# POWER.net
KiCad netlist of a schematic drawn in Altium Designer
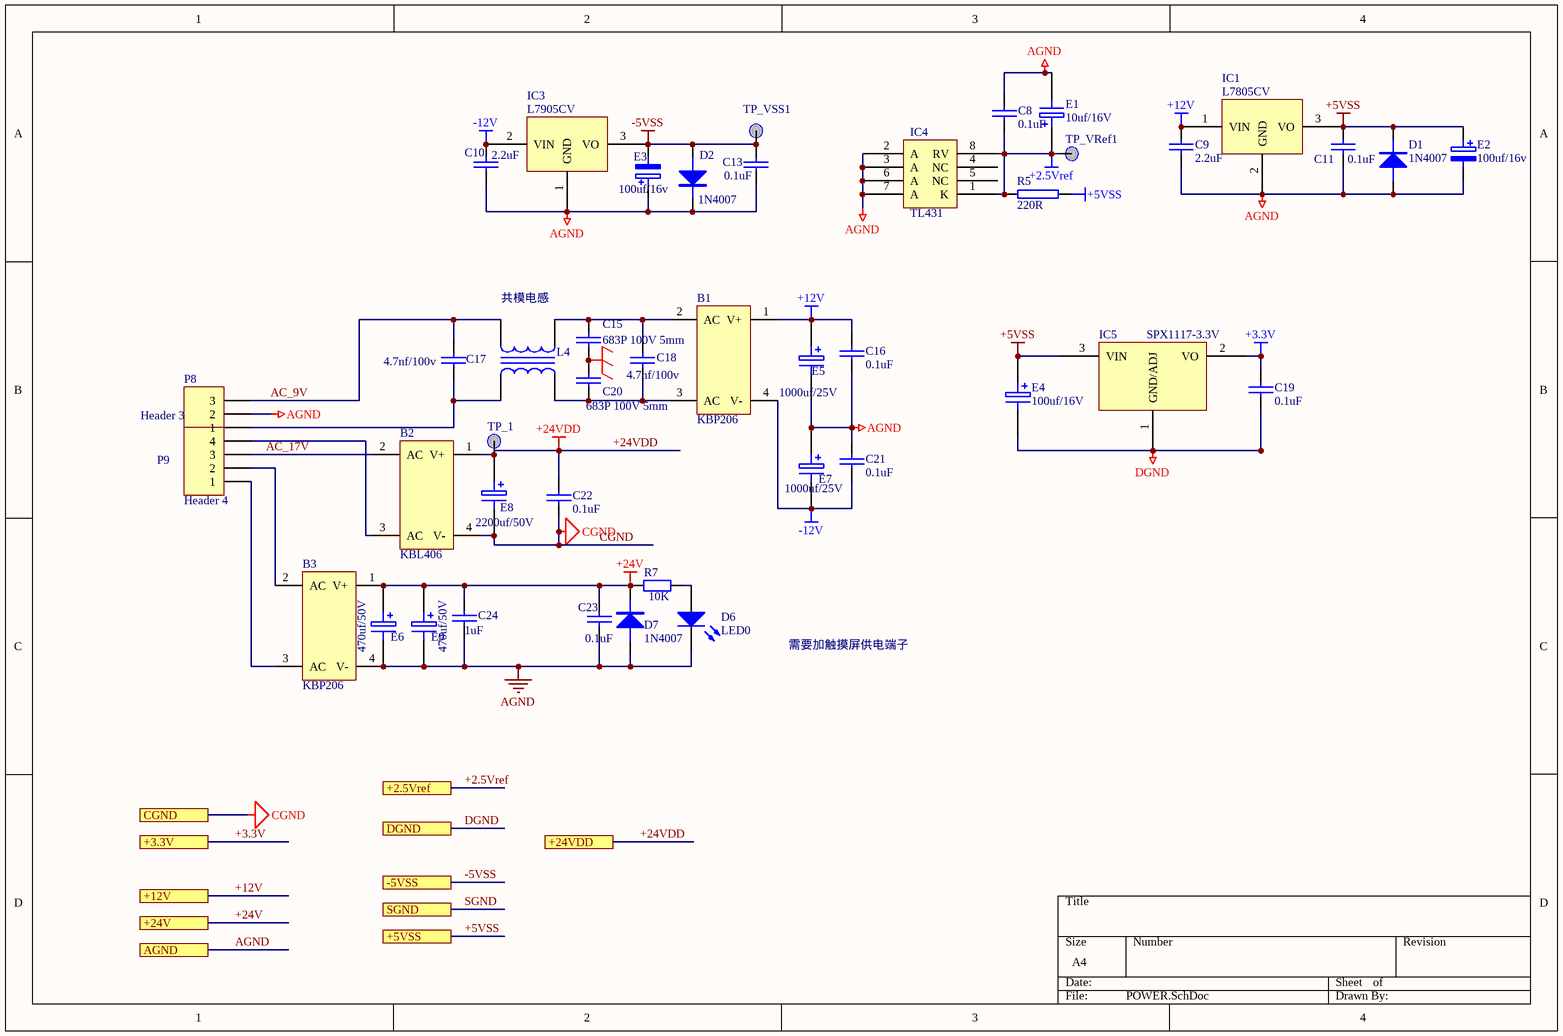
[diagram p0: POWER.SchDoc]

(export (version "E")
  (design (tool "Eeschema 10.0.6"))
  (components
    (comp (ref "B1")
      (value "KBP206")
      (footprint "KBP206")
      (description "品牌： MDD  型号： KBP206  直流反向耐压(Vr)：600V 平均整流电流(Io)：2A 正向压降(Vf)：1.1V@2A 正向浪涌电流(Ifsm)：60A")
      (libsource (lib "*") (part "BRIDGE"))
    )
    (comp (ref "B2")
      (value "KBL406")
      (footprint "KPL406")
      (description "品牌： MDD  型号： KBL406  直流反向耐压(Vr)：600V 平均整流电流(Io)：4A 正向压降(Vf)：1V@4A 正向浪涌电流(Ifsm)：125A")
      (libsource (lib "*") (part "BRIDGE"))
    )
    (comp (ref "B3")
      (value "KBP206")
      (footprint "KBP206")
      (description "品牌： MDD  型号： KBP206  直流反向耐压(Vr)：600V 平均整流电流(Io)：2A 正向压降(Vf)：1.1V@2A 正向浪涌电流(Ifsm)：60A")
      (libsource (lib "*") (part "BRIDGE"))
    )
    (comp (ref "C8") (value "0.1uF") (footprint "0805C") (libsource (lib "*") (part "CAP")))
    (comp (ref "C9")
      (value "2.2uF")
      (footprint "0805C")
      (description "品牌： SAMSUNG(三星) 型号： CL21B225KAFNNNE 容值：2.2uF 精度：±10% 额定电压：25V 材质(温度系数)：X7R 材质:X7R")
      (libsource (lib "*") (part "CAP"))
    )
    (comp (ref "C10")
      (value "2.2uF")
      (footprint "0805C")
      (description "品牌： SAMSUNG(三星) 型号： CL21B225KAFNNNE 容值：2.2uF 精度：±10% 额定电压：25V 材质(温度系数)：X7R 材质:X7R")
      (libsource (lib "*") (part "CAP"))
    )
    (comp (ref "C11")
      (value "0.1uF")
      (footprint "0805C")
      (description "品牌： SAMSUNG(三星) 型号： CL21B104KBCNNNC ：容值：100nF 精度：±10% 额定电压：50V 材质(温度系数)：X7R 材质:X7R")
      (libsource (lib "*") (part "CAP"))
    )
    (comp (ref "C13")
      (value "0.1uF")
      (footprint "0805C")
      (description "品牌： SAMSUNG(三星)    型号： CL10B104KB8NNNC  容值：100nF 精度：±10% 额定电压：50V 材质(温度系数)：X7R 材质:X7R")
      (libsource (lib "*") (part "CAP"))
    )
    (comp (ref "C15")
      (value "683P 100V 5mm")
      (footprint "CP1")
      (description "品牌： muRata(村田) 型号： RCER72A683K1K1H03B  容值：68nF 精度：±10% 额定电压：100V 温度系数：X7R")
      (libsource (lib "*") (part "CAP"))
    )
    (comp (ref "C16")
      (value "0.1uF")
      (footprint "0805C")
      (description "品牌： SAMSUNG(三星)    型号： CL10B104KB8NNNC  容值：100nF 精度：±10% 额定电压：50V 材质(温度系数)：X7R 材质:X7R")
      (libsource (lib "*") (part "CAP"))
    )
    (comp (ref "C17")
      (value "4.7nf/100v")
      (footprint "CP1")
      (description "品牌： muRata(村田) 品牌： muRata(村田)  容值：4.7nF 精度：±10% 额定电压：100V 温度系数：X7R")
      (libsource (lib "*") (part "CAP"))
    )
    (comp (ref "C18")
      (value "4.7nf/100v")
      (footprint "CP1")
      (description "品牌： muRata(村田) 品牌： muRata(村田)  容值：4.7nF 精度：±10% 额定电压：100V 温度系数：X7R")
      (libsource (lib "*") (part "CAP"))
    )
    (comp (ref "C19")
      (value "0.1uF")
      (footprint "0805C")
      (description "Capacitor")
      (libsource (lib "*") (part "CAP"))
    )
    (comp (ref "C20")
      (value "683P 100V 5mm")
      (footprint "CP1")
      (description "品牌： muRata(村田) 型号： RCER72A683K1K1H03B  容值：68nF 精度：±10% 额定电压：100V 温度系数：X7R")
      (libsource (lib "*") (part "CAP"))
    )
    (comp (ref "C21")
      (value "0.1uF")
      (footprint "0805C")
      (description "品牌： SAMSUNG(三星)    型号： CL10B104KB8NNNC  容值：100nF 精度：±10% 额定电压：50V 材质(温度系数)：X7R 材质:X7R")
      (libsource (lib "*") (part "CAP"))
    )
    (comp (ref "C22")
      (value "0.1uF")
      (footprint "0805C")
      (description "品牌： SAMSUNG(三星) 型号： CL21B104KBCNNNC ：容值：100nF 精度：±10% 额定电压：50V 材质(温度系数)：X7R 材质:X7R")
      (libsource (lib "*") (part "CAP"))
    )
    (comp (ref "C23")
      (value "0.1uF")
      (footprint "0805C")
      (description "品牌： SAMSUNG(三星) 型号： CL21B104KBCNNNC ：容值：100nF 精度：±10% 额定电压：50V 材质(温度系数)：X7R 材质:X7R")
      (libsource (lib "*") (part "CAP"))
    )
    (comp (ref "C24")
      (value "1uF")
      (footprint "0805C")
      (description "品牌： SAMSUNG(三星) 型号： CL21B334KBFNNNE 容值：330nF 精度：±10% 额定电压：50V 材质(温度系数)：X7R 材质:X7R")
      (libsource (lib "*") (part "CAP"))
    )
    (comp (ref "D1") (value "1N4007") (footprint "SK24") (libsource (lib "*") (part "DIODE")))
    (comp (ref "D2") (value "1N4007") (footprint "SK24") (libsource (lib "*") (part "DIODE")))
    (comp (ref "D6")
      (value "LED0")
      (footprint "0805LED")
      (description "品牌： 国星光电 型号： NCD0805B2 发光颜色：蓝灯 贴片LED；0805蓝色；2012蓝色；透镜颜色：无色透明；发光角度：130°；功率：72mW；工作温度：-30℃~+85℃；")
      (fields (field (name "PUBLISHER") "Altium Limited"))
      (libsource (lib "Miscellaneous Devices") (part "LED0"))
    )
    (comp (ref "D7") (value "1N4007") (footprint "SK24") (libsource (lib "*") (part "DIODE")))
    (comp (ref "E1")
      (value "10uf/16V")
      (footprint "3528")
      (description "品牌： Kyocera AVX 型号： TAJB106K016RNJ ：容值：10uF 精度：±10% 额定电压：16V 等效串联电阻：2.8Ω@100kHz")
      (libsource (lib "*") (part "ELECTRO1"))
    )
    (comp (ref "E2")
      (value "100uf/16v")
      (footprint "3528")
      (description "品牌： Kyocera AVX 型号： TAJB107M010RNJ  容值：100uF 精度：±20% 额定电压：10V 等效串联电阻：1.4Ω@100kHz")
      (libsource (lib "*") (part "ELECTRO2"))
    )
    (comp (ref "E3")
      (value "100uf/16v")
      (footprint "3528")
      (description "品牌： Kyocera AVX 型号： TAJB107M010RNJ  容值：100uF 精度：±20% 额定电压：10V 等效串联电阻：1.4Ω@100kHz")
      (libsource (lib "*") (part "ELECTRO2"))
    )
    (comp (ref "E4")
      (value "100uf/16V")
      (footprint "3528")
      (description "Electrolytic Capacitor")
      (libsource (lib "*") (part "ELECTRO1"))
    )
    (comp (ref "E5")
      (value "1000uf/25V")
      (footprint "EC5.08-10.5")
      (description "品牌： CX(承兴) 型号： KM108M025G17RR0VH2FP0 容值：1000uF 精度：±20% 额定电压：25V")
      (libsource (lib "*") (part "ELECTRO1"))
    )
    (comp (ref "E6")
      (value "470uf/50V")
      (footprint "EC5.08-10.5")
      (description "品牌： CX(承兴) 型号： KM108M025G17RR0VH2FP0 容值：1000uF 精度：±20% 额定电压：25V")
      (libsource (lib "*") (part "ELECTRO1"))
    )
    (comp (ref "E7")
      (value "1000uf/25V")
      (footprint "EC5.08-10.5")
      (description "品牌： CX(承兴) 型号： KM108M025G17RR0VH2FP0 容值：1000uF 精度：±20% 额定电压：25V")
      (libsource (lib "*") (part "ELECTRO1"))
    )
    (comp (ref "E8")
      (value "2200uf/50V")
      (footprint "EC5.08-13.5")
      (description "品牌： CX(承兴) 型号： KM228M050K30RR0VH2FP0 容值：2200uF 精度：±20% 额定电压：50V")
      (libsource (lib "*") (part "ELECTRO1"))
    )
    (comp (ref "E9")
      (value "470uf/50V")
      (footprint "EC5.08-10.5")
      (description "品牌： CX(承兴) 型号： KM108M025G17RR0VH2FP0 容值：1000uF 精度：±20% 额定电压：25V")
      (libsource (lib "*") (part "ELECTRO1"))
    )
    (comp (ref "IC1")
      (value "L7805CV")
      (footprint "DPAK3")
      (description "品牌： UMW(友台半导体)  型号： L7805CV  输出类型：固定 输出极性：正 最大输入电压：35V 输出电压：5V 输出电流：1.2A")
      (libsource (lib "*") (part "MC78XX"))
    )
    (comp (ref "IC3") (value "L7905CV") (footprint "DPAK3") (libsource (lib "*") (part "MC79XX")))
    (comp (ref "IC4")
      (value "TL431")
      (footprint "SO8")
      (description "品牌： JSMSEMI(杰盛微) 型号： TL431输出类型：可调 输入电压：37V 输出电压：2.5V~36V")
      (libsource (lib "*") (part "TL431-SO8"))
    )
    (comp (ref "IC5") (value "SPX1117-3.3V") (footprint "SOT223") (libsource (lib "*") (part "SPX1117")))
    (comp (ref "L4")
      (value "共模电感")
      (footprint "TRANS")
      (description "UF16 22mH 1.5A 12.5*10")
      (libsource (lib "*") (part "TRANS1"))
    )
    (comp (ref "P8")
      (value "Header 3")
      (footprint "CONN-TH-KF7.62-3P")
      (fields (field (name "PUBLISHER") "Altium Limited"))
      (libsource (lib "Miscellaneous Connectors") (part "Header 3"))
    )
    (comp (ref "P9")
      (value "Header 4")
      (footprint "CONN-TH_KF7.62-4P")
      (fields (field (name "PUBLISHER") "Altium Limited"))
      (libsource (lib "Miscellaneous Connectors") (part "Header 4"))
    )
    (comp (ref "R5")
      (value "220R")
      (footprint "0805R")
      (description "品牌： UNI-ROYAL(厚声) 型号： 0805W8J0221T5E 电阻类型：厚膜电阻 阻值：220Ω 精度：±5% 功率：125mW 温度系数：±100ppm/℃")
      (libsource (lib "*") (part "RES2"))
    )
    (comp (ref "R7")
      (value "10K")
      (footprint "0805R")
      (description "品牌： UNI-ROYAL(厚声) 型号： 0805W8F1002T5E 电阻类型：厚膜电阻 阻值：10kΩ 精度：±1% 功率：125mW 温度系数：±100ppm/℃")
      (fields (field (name "PUBLISHER") "Altium Limited"))
      (libsource (lib "Miscellaneous Devices") (part "Res2"))
    )
    (comp (ref "TP_1") (value "~") (footprint "TPP") (libsource (lib "*") (part "TP")))
    (comp (ref "TP_VRef1") (value "~") (footprint "TPP") (libsource (lib "*") (part "TP")))
    (comp (ref "TP_VSS1") (value "~") (footprint "TPP") (libsource (lib "*") (part "TP")))
  )
  (nets
    (net (code "1") (name "+2.5Vref") (class "Default")
      (node (ref "C8") (pin "2") (pinfunction "2_2") (pintype "passive"))
      (node (ref "E1") (pin "1") (pinfunction "1_1") (pintype "passive"))
      (node (ref "IC4") (pin "1") (pinfunction "K_1") (pintype "passive"))
      (node (ref "IC4") (pin "8") (pinfunction "RV_8") (pintype "passive"))
      (node (ref "R5") (pin "1") (pinfunction "1_1") (pintype "passive"))
      (node (ref "TP_VRef1") (pin "1") (pinfunction "1_1") (pintype "passive"))
    )
    (net (code "2") (name "+3.3V") (class "Default")
      (node (ref "C19") (pin "1") (pinfunction "1_1") (pintype "passive"))
      (node (ref "IC5") (pin "2") (pinfunction "VO_2") (pintype "passive"))
    )
    (net (code "3") (name "+5VSS") (class "Default")
      (node (ref "C11") (pin "1") (pinfunction "1_1") (pintype "passive"))
      (node (ref "D1") (pin "2") (pinfunction "K_2") (pintype "passive"))
      (node (ref "E2") (pin "1") (pintype "passive"))
      (node (ref "E4") (pin "1") (pinfunction "1_1") (pintype "passive"))
      (node (ref "IC1") (pin "3") (pinfunction "VO_3") (pintype "passive"))
      (node (ref "IC5") (pin "3") (pinfunction "VIN_3") (pintype "passive"))
      (node (ref "R5") (pin "2") (pinfunction "2_2") (pintype "passive"))
    )
    (net (code "4") (name "+12V") (class "Default")
      (node (ref "B1") (pin "1") (pinfunction "V+_1") (pintype "passive"))
      (node (ref "C16") (pin "1") (pinfunction "1_1") (pintype "passive"))
      (node (ref "C9") (pin "1") (pinfunction "1_1") (pintype "passive"))
      (node (ref "E5") (pin "1") (pinfunction "1_1") (pintype "passive"))
      (node (ref "IC1") (pin "1") (pinfunction "VIN_1") (pintype "passive"))
    )
    (net (code "5") (name "+24V") (class "Default")
      (node (ref "B3") (pin "1") (pinfunction "V+_1") (pintype "passive"))
      (node (ref "C23") (pin "1") (pinfunction "1_1") (pintype "passive"))
      (node (ref "C24") (pin "1") (pinfunction "1_1") (pintype "passive"))
      (node (ref "D7") (pin "2") (pinfunction "K_2") (pintype "passive"))
      (node (ref "E6") (pin "1") (pinfunction "1_1") (pintype "passive"))
      (node (ref "E9") (pin "1") (pinfunction "1_1") (pintype "passive"))
      (node (ref "R7") (pin "2") (pinfunction "2_2") (pintype "passive"))
    )
    (net (code "6") (name "+24VDD") (class "Default")
      (node (ref "B2") (pin "1") (pinfunction "V+_1") (pintype "passive"))
      (node (ref "C22") (pin "1") (pinfunction "1_1") (pintype "passive"))
      (node (ref "E8") (pin "1") (pinfunction "1_1") (pintype "passive"))
      (node (ref "TP_1") (pin "1") (pinfunction "1_1") (pintype "passive"))
    )
    (net (code "7") (name "-5VSS") (class "Default")
      (node (ref "C13") (pin "1") (pinfunction "1_1") (pintype "passive"))
      (node (ref "D2") (pin "1") (pinfunction "A_1") (pintype "passive"))
      (node (ref "E3") (pin "2") (pintype "passive"))
      (node (ref "IC3") (pin "3") (pinfunction "VO_3") (pintype "passive"))
      (node (ref "TP_VSS1") (pin "1") (pinfunction "1_1") (pintype "passive"))
    )
    (net (code "8") (name "-12V") (class "Default")
      (node (ref "B1") (pin "4") (pinfunction "V-_4") (pintype "passive"))
      (node (ref "C10") (pin "1") (pinfunction "1_1") (pintype "passive"))
      (node (ref "C21") (pin "2") (pinfunction "2_2") (pintype "passive"))
      (node (ref "E7") (pin "2") (pinfunction "2_2") (pintype "passive"))
      (node (ref "IC3") (pin "2") (pinfunction "VIN_2") (pintype "passive"))
    )
    (net (code "10") (name "/AC_9V") (class "Default")
      (node (ref "C17") (pin "1") (pinfunction "1_1") (pintype "passive"))
      (node (ref "L4") (pin "2") (pinfunction "2_2") (pintype "passive"))
      (node (ref "P8") (pin "3") (pinfunction "3_3") (pintype "passive"))
    )
    (net (code "11") (name "/AC_17V") (class "Default")
      (node (ref "B2") (pin "2") (pinfunction "AC_2") (pintype "passive"))
      (node (ref "P9") (pin "3") (pinfunction "3_3") (pintype "passive"))
    )
    (net (code "13") (name "AGND") (class "Default")
      (node (ref "B3") (pin "4") (pinfunction "V-_4") (pintype "passive"))
      (node (ref "C10") (pin "2") (pinfunction "2_2") (pintype "passive"))
      (node (ref "C11") (pin "2") (pinfunction "2_2") (pintype "passive"))
      (node (ref "C13") (pin "2") (pinfunction "2_2") (pintype "passive"))
      (node (ref "C16") (pin "2") (pinfunction "2_2") (pintype "passive"))
      (node (ref "C21") (pin "1") (pinfunction "1_1") (pintype "passive"))
      (node (ref "C23") (pin "2") (pinfunction "2_2") (pintype "passive"))
      (node (ref "C24") (pin "2") (pinfunction "2_2") (pintype "passive"))
      (node (ref "C8") (pin "1") (pinfunction "1_1") (pintype "passive"))
      (node (ref "C9") (pin "2") (pinfunction "2_2") (pintype "passive"))
      (node (ref "D1") (pin "1") (pinfunction "A_1") (pintype "passive"))
      (node (ref "D2") (pin "2") (pinfunction "K_2") (pintype "passive"))
      (node (ref "D6") (pin "2") (pinfunction "K_2") (pintype "passive"))
      (node (ref "D7") (pin "1") (pinfunction "A_1") (pintype "passive"))
      (node (ref "E1") (pin "2") (pinfunction "2_2") (pintype "passive"))
      (node (ref "E2") (pin "2") (pintype "passive"))
      (node (ref "E3") (pin "1") (pintype "passive"))
      (node (ref "E5") (pin "2") (pinfunction "2_2") (pintype "passive"))
      (node (ref "E6") (pin "2") (pinfunction "2_2") (pintype "passive"))
      (node (ref "E7") (pin "1") (pinfunction "1_1") (pintype "passive"))
      (node (ref "E9") (pin "2") (pinfunction "2_2") (pintype "passive"))
      (node (ref "IC1") (pin "2") (pinfunction "GND_2") (pintype "passive"))
      (node (ref "IC3") (pin "1") (pinfunction "GND_1") (pintype "passive"))
      (node (ref "IC4") (pin "2") (pinfunction "A_2") (pintype "passive"))
      (node (ref "IC4") (pin "3") (pinfunction "A_3") (pintype "passive"))
      (node (ref "IC4") (pin "6") (pinfunction "A_6") (pintype "passive"))
      (node (ref "IC4") (pin "7") (pinfunction "A_7") (pintype "passive"))
      (node (ref "P8") (pin "2") (pinfunction "2_2") (pintype "passive"))
    )
    (net (code "14") (name "CGND") (class "Default")
      (node (ref "B2") (pin "4") (pinfunction "V-_4") (pintype "passive"))
      (node (ref "C22") (pin "2") (pinfunction "2_2") (pintype "passive"))
      (node (ref "E8") (pin "2") (pinfunction "2_2") (pintype "passive"))
    )
    (net (code "15") (name "DGND") (class "Default")
      (node (ref "C19") (pin "2") (pinfunction "2_2") (pintype "passive"))
      (node (ref "E4") (pin "2") (pinfunction "2_2") (pintype "passive"))
      (node (ref "IC5") (pin "1") (pinfunction "GND/ADJ_1") (pintype "passive"))
    )
    (net (code "16") (name "EGND") (class "Default")
      (node (ref "C15") (pin "2") (pinfunction "2_2") (pintype "passive"))
      (node (ref "C20") (pin "1") (pinfunction "1_1") (pintype "passive"))
    )
    (net (code "17") (name "Net-(B1-AC-Pad2)") (class "Default")
      (node (ref "B1") (pin "2") (pinfunction "AC_2") (pintype "passive"))
      (node (ref "C15") (pin "1") (pinfunction "1_1") (pintype "passive"))
      (node (ref "C18") (pin "1") (pinfunction "1_1") (pintype "passive"))
      (node (ref "L4") (pin "4") (pinfunction "4_4") (pintype "passive"))
    )
    (net (code "18") (name "Net-(B1-AC-Pad3)") (class "Default")
      (node (ref "B1") (pin "3") (pinfunction "AC_3") (pintype "passive"))
      (node (ref "C18") (pin "2") (pinfunction "2_2") (pintype "passive"))
      (node (ref "C20") (pin "2") (pinfunction "2_2") (pintype "passive"))
      (node (ref "L4") (pin "3") (pinfunction "3_3") (pintype "passive"))
    )
    (net (code "19") (name "Net-(B2-AC-Pad3)") (class "Default")
      (node (ref "B2") (pin "3") (pinfunction "AC_3") (pintype "passive"))
      (node (ref "P9") (pin "4") (pinfunction "4_4") (pintype "passive"))
    )
    (net (code "20") (name "Net-(B3-AC-Pad2)") (class "Default")
      (node (ref "B3") (pin "2") (pinfunction "AC_2") (pintype "passive"))
      (node (ref "P9") (pin "2") (pinfunction "2_2") (pintype "passive"))
    )
    (net (code "21") (name "Net-(B3-AC-Pad3)") (class "Default")
      (node (ref "B3") (pin "3") (pinfunction "AC_3") (pintype "passive"))
      (node (ref "P9") (pin "1") (pinfunction "1_1") (pintype "passive"))
    )
    (net (code "22") (name "Net-(C17-Pad2)") (class "Default")
      (node (ref "C17") (pin "2") (pinfunction "2_2") (pintype "passive"))
      (node (ref "L4") (pin "1") (pinfunction "1_1") (pintype "passive"))
      (node (ref "P8") (pin "1") (pinfunction "1_1") (pintype "passive"))
    )
    (net (code "23") (name "Net-(D6-A)") (class "Default")
      (node (ref "D6") (pin "1") (pinfunction "A_1") (pintype "passive"))
      (node (ref "R7") (pin "1") (pinfunction "1_1") (pintype "passive"))
    )
    (net (code "24") (name "unconnected-(IC4-NC-Pad4)") (class "Default")
      (node (ref "IC4") (pin "4") (pinfunction "NC_4") (pintype "passive"))
    )
    (net (code "25") (name "unconnected-(IC4-NC-Pad5)") (class "Default")
      (node (ref "IC4") (pin "5") (pinfunction "NC_5") (pintype "passive"))
    )
  )
)
